# Schema_Soldeerbout5.net
KiCad netlist of a schematic drawn in Altium Designer
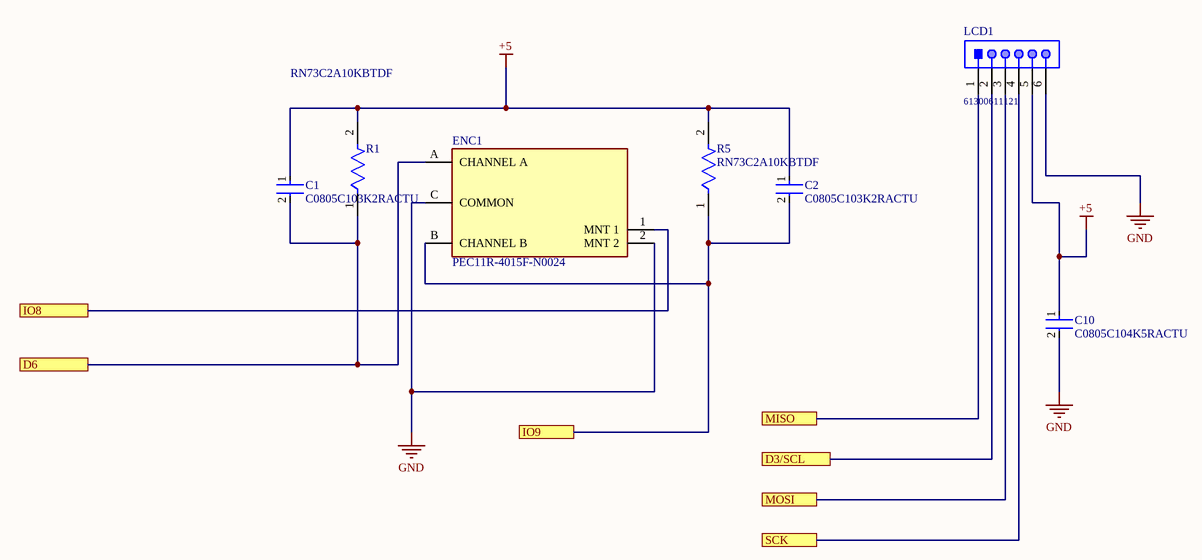
[diagram p0: Schema_Soldeerbout5.SchDoc]

(export (version "E")
  (design (tool "Eeschema 10.0.6"))
  (components
    (comp (ref "C1")
      (value "C0805C103K2RACTU")
      (footprint "FP-C0805C-DN-MFG")
      (description "CAP CER 10000PF 200V X7R 0805")
      (fields
        (field (name "OCTOPART") "https://octopart.com/c0805c103k2ractu-kemet-9138347")
        (field (name "TOLERANCE") "0.1")
      )
      (libsource (lib "Altium Content Vault") (part "b4654b650e69147ec39a6b967a45e02"))
    )
    (comp (ref "C2")
      (value "C0805C103K2RACTU")
      (footprint "FP-C0805C-DN-MFG")
      (description "CAP CER 10000PF 200V X7R 0805")
      (fields
        (field (name "OCTOPART") "https://octopart.com/c0805c103k2ractu-kemet-9138347")
        (field (name "TOLERANCE") "0.1")
      )
      (libsource (lib "Altium Content Vault") (part "b4654b650e69147ec39a6b967a45e02"))
    )
    (comp (ref "C10")
      (value "C0805C104K5RACTU")
      (footprint "FP-C0805C-DN-MFG")
      (description "CAP CER 0.1UF 50V X7R 0805")
      (fields
        (field (name "MANUFACTURER") "KEMET")
        (field (name "OCTOPART") "https://octopart.com/c0805c104k5ractu-kemet-143926")
      )
      (libsource (lib "Altium Content Vault") (part "b4654b650e69147ec39a6b967a45e02"))
    )
    (comp (ref "ENC1")
      (value "PEC11R-4015F-N0024")
      (footprint "FP-PEC11R-4015F-N0024-MFG")
      (description "ROTARY ENCODER MECHANICAL 24PPR")
      (fields
        (field (name "MANUFACTURER") "Bourns")
        (field (name "OCTOPART") "https://octopart.com/pec11r-4015f-n0024-bourns-26648251")
      )
      (libsource (lib "Altium Content Vault") (part "714335eeadb64c170d88fa1cfc7421d"))
    )
    (comp (ref "LCD1")
      (value "61300611121")
      (footprint "61300611121")
      (description "THT Vertical Pin Header WR-PHD, Pitch 2.54 mm, Single Row, 6 pins")
      (fields (field (name "MANUFACTURER") "Wurth Elektronik") (field (name "PUBLISHER") "WurthElektronik"))
      (libsource (lib "Altium Content Vault") (part "WE-CN-1P-M-R6"))
    )
    (comp (ref "R1")
      (value "RN73C2A10KBTDF")
      (footprint "FP-RN732A-MFG")
      (description "SMD Chip Resistor, Thin Film, 10KΩ, 100 V, 0805 [2012 Metric], 100 mW, 0.1%, RN73 Series")
      (fields
        (field (name "OCTOPART") "https://octopart.com/rn73c2a10kbtdf-te+connectivity-21400356")
        (field (name "MANUFACTURER") "TE Connectivity")
      )
      (libsource (lib "Altium Content Vault") (part "1029c3af85768c4190bb7ad29bc67b5"))
    )
    (comp (ref "R5")
      (value "RN73C2A10KBTDF")
      (footprint "FP-RN732A-MFG")
      (description "SMD Chip Resistor, Thin Film, 10KΩ, 100 V, 0805 [2012 Metric], 100 mW, 0.1%, RN73 Series")
      (fields
        (field (name "OCTOPART") "https://octopart.com/rn73c2a10kbtdf-te+connectivity-21400356")
        (field (name "MANUFACTURER") "TE Connectivity")
      )
      (libsource (lib "Altium Content Vault") (part "1029c3af85768c4190bb7ad29bc67b5"))
    )
  )
  (nets
    (net (code "1") (name "+5") (class "Default")
      (node (ref "C1") (pin "1") (pinfunction "1_1") (pintype "passive"))
      (node (ref "C10") (pin "1") (pinfunction "1_1") (pintype "passive"))
      (node (ref "C2") (pin "1") (pinfunction "1_1") (pintype "passive"))
      (node (ref "LCD1") (pin "5") (pinfunction "5_5") (pintype "passive"))
      (node (ref "R1") (pin "2") (pinfunction "2_2") (pintype "passive"))
      (node (ref "R5") (pin "2") (pinfunction "2_2") (pintype "passive"))
    )
    (net (code "2") (name "/D3{slash}SCL") (class "Default")
      (node (ref "LCD1") (pin "2") (pinfunction "2_2") (pintype "passive"))
    )
    (net (code "3") (name "/D6") (class "Default")
      (node (ref "C1") (pin "2") (pinfunction "2_2") (pintype "passive"))
      (node (ref "ENC1") (pin "A") (pinfunction "CHANNEL_A_A") (pintype "passive"))
      (node (ref "R1") (pin "1") (pinfunction "1_1") (pintype "passive"))
    )
    (net (code "4") (name "/IO8") (class "Default")
      (node (ref "ENC1") (pin "1") (pinfunction "MNT_1_1") (pintype "passive"))
    )
    (net (code "5") (name "/IO9") (class "Default")
      (node (ref "C2") (pin "2") (pinfunction "2_2") (pintype "passive"))
      (node (ref "ENC1") (pin "B") (pinfunction "CHANNEL_B_B") (pintype "passive"))
      (node (ref "R5") (pin "1") (pinfunction "1_1") (pintype "passive"))
    )
    (net (code "6") (name "/MISO") (class "Default")
      (node (ref "LCD1") (pin "1") (pinfunction "1_1") (pintype "passive"))
    )
    (net (code "7") (name "/MOSI") (class "Default")
      (node (ref "LCD1") (pin "3") (pinfunction "3_3") (pintype "passive"))
    )
    (net (code "8") (name "/SCK") (class "Default")
      (node (ref "LCD1") (pin "4") (pinfunction "4_4") (pintype "passive"))
    )
    (net (code "9") (name "GND") (class "Default")
      (node (ref "C10") (pin "2") (pinfunction "2_2") (pintype "passive"))
      (node (ref "ENC1") (pin "2") (pinfunction "MNT_2_2") (pintype "passive"))
      (node (ref "ENC1") (pin "C") (pinfunction "COMMON_C") (pintype "passive"))
      (node (ref "LCD1") (pin "6") (pinfunction "6_6") (pintype "passive"))
    )
  )
)
